# AudioBoard.net
KiCad netlist of a schematic drawn in EAGLE
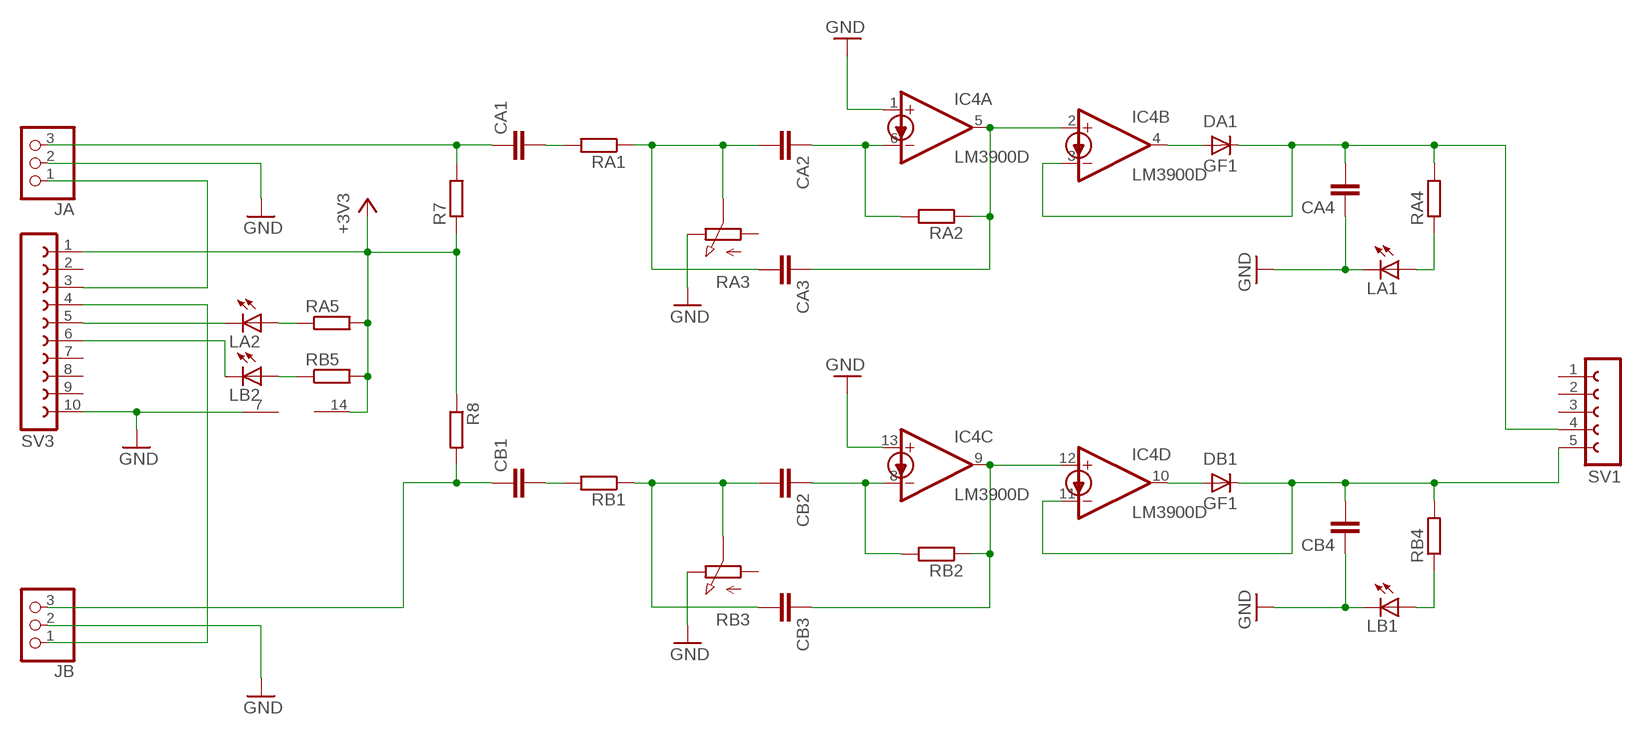
[diagram p0: schematic, sheet 1]

(export (version "E")
  (design (tool "Eeschema 10.0.6"))
  (components
    (comp (ref "CA1")
      (value "C-EUC0402K")
      (footprint "eagle-import:C0402K")
      (libsource (lib "eagle-import") (part "C-EUC0402K"))
    )
    (comp (ref "CA2")
      (value "C-EUC0402K")
      (footprint "eagle-import:C0402K")
      (libsource (lib "eagle-import") (part "C-EUC0402K"))
    )
    (comp (ref "CA3")
      (value "C-EUC0402K")
      (footprint "eagle-import:C0402K")
      (libsource (lib "eagle-import") (part "C-EUC0402K"))
    )
    (comp (ref "CA4")
      (value "C-EUC0402K")
      (footprint "eagle-import:C0402K")
      (libsource (lib "eagle-import") (part "C-EUC0402K"))
    )
    (comp (ref "CB1")
      (value "C-EUC0402K")
      (footprint "eagle-import:C0402K")
      (libsource (lib "eagle-import") (part "C-EUC0402K"))
    )
    (comp (ref "CB2")
      (value "C-EUC0402K")
      (footprint "eagle-import:C0402K")
      (libsource (lib "eagle-import") (part "C-EUC0402K"))
    )
    (comp (ref "CB3")
      (value "C-EUC0402K")
      (footprint "eagle-import:C0402K")
      (libsource (lib "eagle-import") (part "C-EUC0402K"))
    )
    (comp (ref "CB4")
      (value "C-EUC0402K")
      (footprint "eagle-import:C0402K")
      (libsource (lib "eagle-import") (part "C-EUC0402K"))
    )
    (comp (ref "DA1")
      (value "GF1")
      (footprint "eagle-import:SMA-DO214AC")
      (libsource (lib "eagle-import") (part "GF1"))
    )
    (comp (ref "DB1")
      (value "GF1")
      (footprint "eagle-import:SMA-DO214AC")
      (libsource (lib "eagle-import") (part "GF1"))
    )
    (comp (ref "IC4")
      (value "LM3900D")
      (footprint "eagle-import:SO14")
      (libsource (lib "eagle-import") (part "LM3900D"))
    )
    (comp (ref "JA")
      (value "PINHD-1X3/90")
      (footprint "eagle-import:1X03_90")
      (libsource (lib "eagle-import") (part "PINHD-1X3/90"))
    )
    (comp (ref "JB")
      (value "PINHD-1X3/90")
      (footprint "eagle-import:1X03_90")
      (libsource (lib "eagle-import") (part "PINHD-1X3/90"))
    )
    (comp (ref "LA1")
      (value "LEDCHIPLED_0805")
      (footprint "eagle-import:CHIPLED_0805")
      (libsource (lib "eagle-import") (part "LEDCHIPLED_0805"))
    )
    (comp (ref "LA2")
      (value "LEDCHIPLED_0805")
      (footprint "eagle-import:CHIPLED_0805")
      (libsource (lib "eagle-import") (part "LEDCHIPLED_0805"))
    )
    (comp (ref "LB1")
      (value "LEDCHIPLED_0805")
      (footprint "eagle-import:CHIPLED_0805")
      (libsource (lib "eagle-import") (part "LEDCHIPLED_0805"))
    )
    (comp (ref "LB2")
      (value "LEDCHIPLED_0805")
      (footprint "eagle-import:CHIPLED_0805")
      (libsource (lib "eagle-import") (part "LEDCHIPLED_0805"))
    )
    (comp (ref "R7")
      (value "R-EU_R0402")
      (footprint "eagle-import:R0402")
      (libsource (lib "eagle-import") (part "R-EU_R0402"))
    )
    (comp (ref "R8")
      (value "R-EU_R0402")
      (footprint "eagle-import:R0402")
      (libsource (lib "eagle-import") (part "R-EU_R0402"))
    )
    (comp (ref "RA1")
      (value "R-EU_R0402")
      (footprint "eagle-import:R0402")
      (libsource (lib "eagle-import") (part "R-EU_R0402"))
    )
    (comp (ref "RA2")
      (value "R-EU_R0402")
      (footprint "eagle-import:R0402")
      (libsource (lib "eagle-import") (part "R-EU_R0402"))
    )
    (comp (ref "RA3")
      (value "PC25")
      (footprint "eagle-import:PC25")
      (fields (field (name "MF") "CLAROSTAT") (field (name "MPN") "308NPC25KS"))
      (libsource (lib "eagle-import") (part "PC25"))
    )
    (comp (ref "RA4")
      (value "R-EU_R0402")
      (footprint "eagle-import:R0402")
      (libsource (lib "eagle-import") (part "R-EU_R0402"))
    )
    (comp (ref "RA5")
      (value "R-EU_R0402")
      (footprint "eagle-import:R0402")
      (libsource (lib "eagle-import") (part "R-EU_R0402"))
    )
    (comp (ref "RB1")
      (value "R-EU_R0402")
      (footprint "eagle-import:R0402")
      (libsource (lib "eagle-import") (part "R-EU_R0402"))
    )
    (comp (ref "RB2")
      (value "R-EU_R0402")
      (footprint "eagle-import:R0402")
      (libsource (lib "eagle-import") (part "R-EU_R0402"))
    )
    (comp (ref "RB3")
      (value "PC25")
      (footprint "eagle-import:PC25")
      (fields (field (name "MF") "CLAROSTAT") (field (name "MPN") "308NPC25KS"))
      (libsource (lib "eagle-import") (part "PC25"))
    )
    (comp (ref "RB4")
      (value "R-EU_R0402")
      (footprint "eagle-import:R0402")
      (libsource (lib "eagle-import") (part "R-EU_R0402"))
    )
    (comp (ref "RB5")
      (value "R-EU_R0402")
      (footprint "eagle-import:R0402")
      (libsource (lib "eagle-import") (part "R-EU_R0402"))
    )
    (comp (ref "SV1")
      (value "FE05-1")
      (footprint "eagle-import:FE05-1")
      (libsource (lib "eagle-import") (part "FE05-1"))
    )
    (comp (ref "SV3")
      (value "FE10-1")
      (footprint "eagle-import:FE10")
      (libsource (lib "eagle-import") (part "FE10-1"))
    )
  )
  (nets
    (net (code "1") (name "+3V3") (class "Default")
      (node (ref "IC4") (pin "14") (pinfunction "V+_14") (pintype "power_in"))
      (node (ref "R7") (pin "1") (pinfunction "1_1") (pintype "passive"))
      (node (ref "R8") (pin "1") (pinfunction "1_1") (pintype "passive"))
      (node (ref "RA5") (pin "2") (pinfunction "2_2") (pintype "passive"))
      (node (ref "RB5") (pin "2") (pinfunction "2_2") (pintype "passive"))
      (node (ref "SV3") (pin "1") (pinfunction "1_1") (pintype "passive"))
    )
    (net (code "2") (name "GND") (class "Default")
      (node (ref "CA4") (pin "1") (pinfunction "1_1") (pintype "passive"))
      (node (ref "CB4") (pin "1") (pinfunction "1_1") (pintype "passive"))
      (node (ref "IC4") (pin "1") (pinfunction "+IN_1") (pintype "input"))
      (node (ref "IC4") (pin "13") (pinfunction "+IN_13") (pintype "input"))
      (node (ref "IC4") (pin "7") (pinfunction "GND_7") (pintype "power_in"))
      (node (ref "JA") (pin "2") (pinfunction "2_2") (pintype "passive"))
      (node (ref "JB") (pin "2") (pinfunction "2_2") (pintype "passive"))
      (node (ref "LA1") (pin "C") (pinfunction "C_C") (pintype "passive"))
      (node (ref "LB1") (pin "C") (pinfunction "C_C") (pintype "passive"))
      (node (ref "RA3") (pin "E") (pinfunction "E_E") (pintype "passive"))
      (node (ref "RB3") (pin "E") (pinfunction "E_E") (pintype "passive"))
      (node (ref "SV3") (pin "10") (pinfunction "10_10") (pintype "passive"))
    )
    (net (code "3") (name "Net-(CA1-Pad1)") (class "Default")
      (node (ref "CA1") (pin "1") (pinfunction "1_1") (pintype "passive"))
      (node (ref "JA") (pin "3") (pinfunction "3_3") (pintype "passive"))
      (node (ref "R7") (pin "2") (pinfunction "2_2") (pintype "passive"))
    )
    (net (code "4") (name "Net-(CA1-Pad2)") (class "Default")
      (node (ref "CA1") (pin "2") (pinfunction "2_2") (pintype "passive"))
      (node (ref "RA1") (pin "2") (pinfunction "2_2") (pintype "passive"))
    )
    (net (code "5") (name "Net-(CA2-Pad2)") (class "Default")
      (node (ref "CA2") (pin "2") (pinfunction "2_2") (pintype "passive"))
      (node (ref "CA3") (pin "2") (pinfunction "2_2") (pintype "passive"))
      (node (ref "RA1") (pin "1") (pinfunction "1_1") (pintype "passive"))
      (node (ref "RA3") (pin "S") (pinfunction "S_S") (pintype "passive"))
    )
    (net (code "6") (name "Net-(CB1-Pad1)") (class "Default")
      (node (ref "CB1") (pin "1") (pinfunction "1_1") (pintype "passive"))
      (node (ref "JB") (pin "3") (pinfunction "3_3") (pintype "passive"))
      (node (ref "R8") (pin "2") (pinfunction "2_2") (pintype "passive"))
    )
    (net (code "7") (name "Net-(CB1-Pad2)") (class "Default")
      (node (ref "CB1") (pin "2") (pinfunction "2_2") (pintype "passive"))
      (node (ref "RB1") (pin "2") (pinfunction "2_2") (pintype "passive"))
    )
    (net (code "8") (name "Net-(CB2-Pad2)") (class "Default")
      (node (ref "CB2") (pin "2") (pinfunction "2_2") (pintype "passive"))
      (node (ref "CB3") (pin "2") (pinfunction "2_2") (pintype "passive"))
      (node (ref "RB1") (pin "1") (pinfunction "1_1") (pintype "passive"))
      (node (ref "RB3") (pin "S") (pinfunction "S_S") (pintype "passive"))
    )
    (net (code "9") (name "Net-(DA1-C)") (class "Default")
      (node (ref "CA4") (pin "2") (pinfunction "2_2") (pintype "passive"))
      (node (ref "DA1") (pin "K") (pinfunction "C_K") (pintype "passive"))
      (node (ref "IC4") (pin "3") (pinfunction "-IN_3") (pintype "input"))
      (node (ref "RA4") (pin "2") (pinfunction "2_2") (pintype "passive"))
      (node (ref "SV1") (pin "4") (pinfunction "4_4") (pintype "passive"))
    )
    (net (code "10") (name "Net-(DB1-C)") (class "Default")
      (node (ref "CB4") (pin "2") (pinfunction "2_2") (pintype "passive"))
      (node (ref "DB1") (pin "K") (pinfunction "C_K") (pintype "passive"))
      (node (ref "IC4") (pin "11") (pinfunction "-IN_11") (pintype "input"))
      (node (ref "RB4") (pin "2") (pinfunction "2_2") (pintype "passive"))
      (node (ref "SV1") (pin "5") (pinfunction "5_5") (pintype "passive"))
    )
    (net (code "11") (name "Net-(IC4A--IN)") (class "Default")
      (node (ref "CA2") (pin "1") (pinfunction "1_1") (pintype "passive"))
      (node (ref "IC4") (pin "6") (pinfunction "-IN_6") (pintype "input"))
      (node (ref "RA2") (pin "2") (pinfunction "2_2") (pintype "passive"))
    )
    (net (code "12") (name "Net-(IC4A-OUT)") (class "Default")
      (node (ref "CA3") (pin "1") (pinfunction "1_1") (pintype "passive"))
      (node (ref "IC4") (pin "2") (pinfunction "+IN_2") (pintype "input"))
      (node (ref "IC4") (pin "5") (pinfunction "OUT_5") (pintype "output"))
      (node (ref "RA2") (pin "1") (pinfunction "1_1") (pintype "passive"))
    )
    (net (code "13") (name "Net-(IC4B-OUT)") (class "Default")
      (node (ref "DA1") (pin "A") (pinfunction "A_A") (pintype "passive"))
      (node (ref "IC4") (pin "4") (pinfunction "OUT_4") (pintype "output"))
    )
    (net (code "14") (name "Net-(IC4C--IN)") (class "Default")
      (node (ref "CB2") (pin "1") (pinfunction "1_1") (pintype "passive"))
      (node (ref "IC4") (pin "8") (pinfunction "-IN_8") (pintype "input"))
      (node (ref "RB2") (pin "2") (pinfunction "2_2") (pintype "passive"))
    )
    (net (code "15") (name "Net-(IC4C-OUT)") (class "Default")
      (node (ref "CB3") (pin "1") (pinfunction "1_1") (pintype "passive"))
      (node (ref "IC4") (pin "12") (pinfunction "+IN_12") (pintype "input"))
      (node (ref "IC4") (pin "9") (pinfunction "OUT_9") (pintype "output"))
      (node (ref "RB2") (pin "1") (pinfunction "1_1") (pintype "passive"))
    )
    (net (code "16") (name "Net-(IC4D-OUT)") (class "Default")
      (node (ref "DB1") (pin "A") (pinfunction "A_A") (pintype "passive"))
      (node (ref "IC4") (pin "10") (pinfunction "OUT_10") (pintype "output"))
    )
    (net (code "17") (name "Net-(JA-Pad1)") (class "Default")
      (node (ref "JA") (pin "1") (pinfunction "1_1") (pintype "passive"))
      (node (ref "SV3") (pin "3") (pinfunction "3_3") (pintype "passive"))
    )
    (net (code "18") (name "Net-(JB-Pad1)") (class "Default")
      (node (ref "JB") (pin "1") (pinfunction "1_1") (pintype "passive"))
      (node (ref "SV3") (pin "4") (pinfunction "4_4") (pintype "passive"))
    )
    (net (code "19") (name "Net-(LA1-PadA)") (class "Default")
      (node (ref "LA1") (pin "A") (pinfunction "A_A") (pintype "passive"))
      (node (ref "RA4") (pin "1") (pinfunction "1_1") (pintype "passive"))
    )
    (net (code "20") (name "Net-(LA2-PadA)") (class "Default")
      (node (ref "LA2") (pin "A") (pinfunction "A_A") (pintype "passive"))
      (node (ref "RA5") (pin "1") (pinfunction "1_1") (pintype "passive"))
    )
    (net (code "21") (name "Net-(LA2-PadC)") (class "Default")
      (node (ref "LA2") (pin "C") (pinfunction "C_C") (pintype "passive"))
      (node (ref "SV3") (pin "5") (pinfunction "5_5") (pintype "passive"))
    )
    (net (code "22") (name "Net-(LB1-PadA)") (class "Default")
      (node (ref "LB1") (pin "A") (pinfunction "A_A") (pintype "passive"))
      (node (ref "RB4") (pin "1") (pinfunction "1_1") (pintype "passive"))
    )
    (net (code "23") (name "Net-(LB2-PadA)") (class "Default")
      (node (ref "LB2") (pin "A") (pinfunction "A_A") (pintype "passive"))
      (node (ref "RB5") (pin "1") (pinfunction "1_1") (pintype "passive"))
    )
    (net (code "24") (name "Net-(LB2-PadC)") (class "Default")
      (node (ref "LB2") (pin "C") (pinfunction "C_C") (pintype "passive"))
      (node (ref "SV3") (pin "6") (pinfunction "6_6") (pintype "passive"))
    )
    (net (code "25") (name "unconnected-(RA3-PadA)") (class "Default")
      (node (ref "RA3") (pin "A") (pinfunction "A_A") (pintype "passive"))
    )
    (net (code "26") (name "unconnected-(RB3-PadA)") (class "Default")
      (node (ref "RB3") (pin "A") (pinfunction "A_A") (pintype "passive"))
    )
    (net (code "27") (name "unconnected-(SV1-Pad1)") (class "Default")
      (node (ref "SV1") (pin "1") (pinfunction "1_1") (pintype "passive"))
    )
    (net (code "28") (name "unconnected-(SV1-Pad2)") (class "Default")
      (node (ref "SV1") (pin "2") (pinfunction "2_2") (pintype "passive"))
    )
    (net (code "29") (name "unconnected-(SV1-Pad3)") (class "Default")
      (node (ref "SV1") (pin "3") (pinfunction "3_3") (pintype "passive"))
    )
    (net (code "30") (name "unconnected-(SV3-Pad2)") (class "Default")
      (node (ref "SV3") (pin "2") (pinfunction "2_2") (pintype "passive"))
    )
    (net (code "31") (name "unconnected-(SV3-Pad7)") (class "Default")
      (node (ref "SV3") (pin "7") (pinfunction "7_7") (pintype "passive"))
    )
    (net (code "32") (name "unconnected-(SV3-Pad8)") (class "Default")
      (node (ref "SV3") (pin "8") (pinfunction "8_8") (pintype "passive"))
    )
    (net (code "33") (name "unconnected-(SV3-Pad9)") (class "Default")
      (node (ref "SV3") (pin "9") (pinfunction "9_9") (pintype "passive"))
    )
  )
)
